# VHN-B.net
KiCad netlist of a schematic drawn in EAGLE
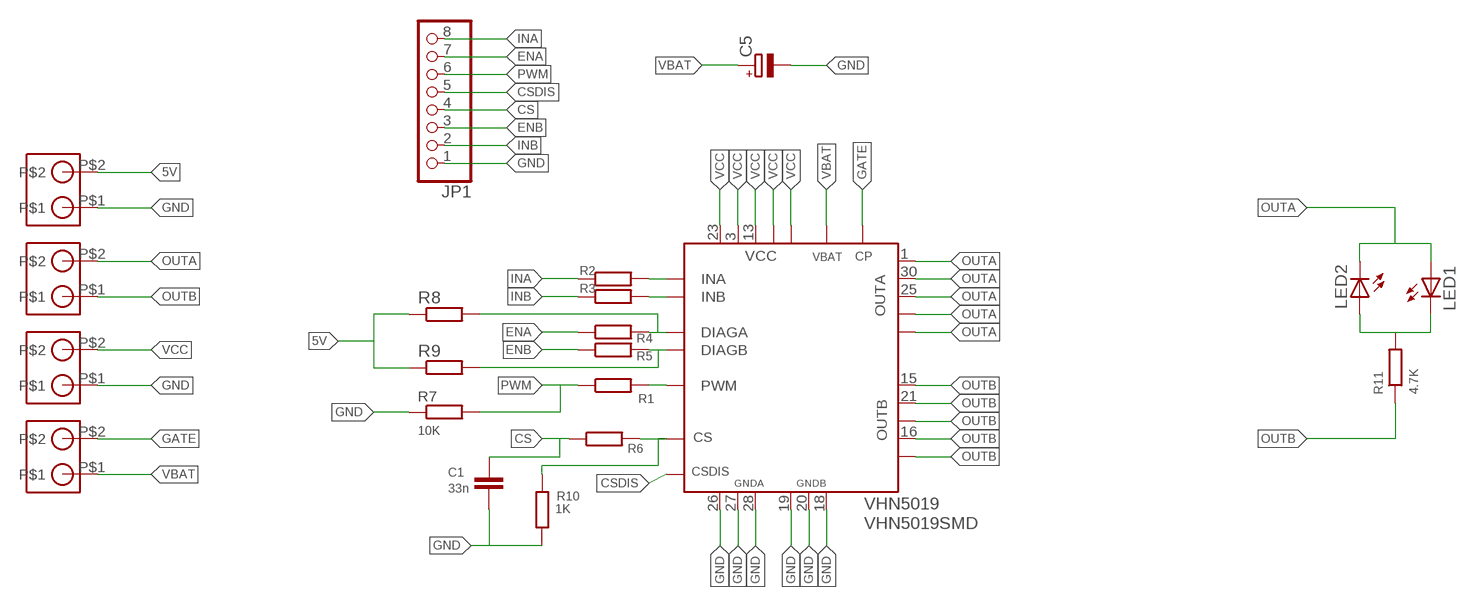
[diagram p0: schematic, sheet 1]

(export (version "E")
  (design (tool "Eeschema 10.0.6"))
  (components
    (comp (ref "C1")
      (value "33n")
      (footprint "eagle-import:C0402")
      (libsource (lib "eagle-import") (part "C-EUC0402"))
    )
    (comp (ref "C5")
      (value "CPOL-EUE2,5-6E")
      (footprint "eagle-import:E2,5-6E")
      (libsource (lib "eagle-import") (part "CPOL-EUE2,5-6E"))
    )
    (comp (ref "JP1")
      (value "PINHD-1X8")
      (footprint "eagle-import:1X08")
      (libsource (lib "eagle-import") (part "PINHD-1X8"))
    )
    (comp (ref "LED1")
      (value "LEDCHIPLED_0603")
      (footprint "eagle-import:CHIPLED_0603")
      (libsource (lib "eagle-import") (part "LEDCHIPLED_0603"))
    )
    (comp (ref "LED2")
      (value "LEDCHIPLED_0603")
      (footprint "eagle-import:CHIPLED_0603")
      (libsource (lib "eagle-import") (part "LEDCHIPLED_0603"))
    )
    (comp (ref "R1")
      (value "R-EU_R0402")
      (footprint "eagle-import:R0402")
      (libsource (lib "eagle-import") (part "R-EU_R0402"))
    )
    (comp (ref "R2")
      (value "R-EU_R0402")
      (footprint "eagle-import:R0402")
      (libsource (lib "eagle-import") (part "R-EU_R0402"))
    )
    (comp (ref "R3")
      (value "R-EU_R0402")
      (footprint "eagle-import:R0402")
      (libsource (lib "eagle-import") (part "R-EU_R0402"))
    )
    (comp (ref "R4")
      (value "R-EU_R0402")
      (footprint "eagle-import:R0402")
      (libsource (lib "eagle-import") (part "R-EU_R0402"))
    )
    (comp (ref "R5")
      (value "R-EU_R0402")
      (footprint "eagle-import:R0402")
      (libsource (lib "eagle-import") (part "R-EU_R0402"))
    )
    (comp (ref "R6")
      (value "R-EU_R0402")
      (footprint "eagle-import:R0402")
      (libsource (lib "eagle-import") (part "R-EU_R0402"))
    )
    (comp (ref "R7")
      (value "10K")
      (footprint "eagle-import:R0402")
      (libsource (lib "eagle-import") (part "R-EU_R0402"))
    )
    (comp (ref "R8")
      (value "R-EU_R0402")
      (footprint "eagle-import:R0402")
      (libsource (lib "eagle-import") (part "R-EU_R0402"))
    )
    (comp (ref "R9")
      (value "R-EU_R0402")
      (footprint "eagle-import:R0402")
      (libsource (lib "eagle-import") (part "R-EU_R0402"))
    )
    (comp (ref "R10")
      (value "1K")
      (footprint "eagle-import:R0402")
      (libsource (lib "eagle-import") (part "R-EU_R0402"))
    )
    (comp (ref "R11")
      (value "4.7K")
      (footprint "eagle-import:R0402")
      (libsource (lib "eagle-import") (part "R-EU_R0402"))
    )
    (comp (ref "U$1")
      (value "PBCON")
      (footprint "eagle-import:02P")
      (libsource (lib "eagle-import") (part "PBCON"))
    )
    (comp (ref "U$2")
      (value "PBCON")
      (footprint "eagle-import:02P")
      (libsource (lib "eagle-import") (part "PBCON"))
    )
    (comp (ref "U$3")
      (value "PBCON")
      (footprint "eagle-import:02P")
      (libsource (lib "eagle-import") (part "PBCON"))
    )
    (comp (ref "U$4")
      (value "PBCON")
      (footprint "eagle-import:02P")
      (libsource (lib "eagle-import") (part "PBCON"))
    )
    (comp (ref "VHN5019")
      (value "VHN5019SMD")
      (footprint "eagle-import:SO-30")
      (libsource (lib "eagle-import") (part "VHN5019SMD"))
    )
  )
  (nets
    (net (code "1") (name "5V") (class "Default")
      (node (ref "R8") (pin "1") (pinfunction "1_1") (pintype "passive"))
      (node (ref "R9") (pin "1") (pinfunction "1_1") (pintype "passive"))
      (node (ref "U$4") (pin "P$2") (pinfunction "P$2_P$2") (pintype "bidirectional"))
    )
    (net (code "2") (name "CS") (class "Default")
      (node (ref "C1") (pin "1") (pinfunction "1_1") (pintype "passive"))
      (node (ref "JP1") (pin "4") (pinfunction "4_4") (pintype "passive"))
      (node (ref "R6") (pin "1") (pinfunction "1_1") (pintype "passive"))
    )
    (net (code "3") (name "CSDIS") (class "Default")
      (node (ref "JP1") (pin "5") (pinfunction "5_5") (pintype "passive"))
      (node (ref "VHN5019") (pin "6") (pinfunction "CSDIS_6") (pintype "bidirectional"))
    )
    (net (code "4") (name "ENA") (class "Default")
      (node (ref "JP1") (pin "7") (pinfunction "7_7") (pintype "passive"))
      (node (ref "R4") (pin "1") (pinfunction "1_1") (pintype "passive"))
    )
    (net (code "5") (name "ENB") (class "Default")
      (node (ref "JP1") (pin "3") (pinfunction "3_3") (pintype "passive"))
      (node (ref "R5") (pin "1") (pinfunction "1_1") (pintype "passive"))
    )
    (net (code "6") (name "GATE") (class "Default")
      (node (ref "U$3") (pin "P$2") (pinfunction "P$2_P$2") (pintype "bidirectional"))
      (node (ref "VHN5019") (pin "11") (pinfunction "CP_11") (pintype "bidirectional"))
    )
    (net (code "7") (name "GND") (class "Default")
      (node (ref "C1") (pin "2") (pinfunction "2_2") (pintype "passive"))
      (node (ref "C5") (pin "-") (pinfunction "-_-") (pintype "passive"))
      (node (ref "JP1") (pin "1") (pinfunction "1_1") (pintype "passive"))
      (node (ref "R10") (pin "1") (pinfunction "1_1") (pintype "passive"))
      (node (ref "R7") (pin "1") (pinfunction "1_1") (pintype "passive"))
      (node (ref "U$1") (pin "P$1") (pinfunction "P$1_P$1") (pintype "bidirectional"))
      (node (ref "U$4") (pin "P$1") (pinfunction "P$1_P$1") (pintype "bidirectional"))
      (node (ref "VHN5019") (pin "18") (pinfunction "GNDB_18") (pintype "power_in"))
      (node (ref "VHN5019") (pin "19") (pinfunction "GNDB_19") (pintype "power_in"))
      (node (ref "VHN5019") (pin "20") (pinfunction "GNDB_20") (pintype "power_in"))
      (node (ref "VHN5019") (pin "26") (pinfunction "GNDA_26") (pintype "power_in"))
      (node (ref "VHN5019") (pin "27") (pinfunction "GNDA_27") (pintype "power_in"))
      (node (ref "VHN5019") (pin "28") (pinfunction "GNDA_28") (pintype "power_in"))
    )
    (net (code "8") (name "INA") (class "Default")
      (node (ref "JP1") (pin "8") (pinfunction "8_8") (pintype "passive"))
      (node (ref "R2") (pin "1") (pinfunction "1_1") (pintype "passive"))
    )
    (net (code "9") (name "INB") (class "Default")
      (node (ref "JP1") (pin "2") (pinfunction "2_2") (pintype "passive"))
      (node (ref "R3") (pin "1") (pinfunction "1_1") (pintype "passive"))
    )
    (net (code "10") (name "Net-(LED1-PadC)") (class "Default")
      (node (ref "LED1") (pin "C") (pinfunction "C_C") (pintype "passive"))
      (node (ref "LED2") (pin "A") (pinfunction "A_A") (pintype "passive"))
      (node (ref "R11") (pin "2") (pinfunction "2_2") (pintype "passive"))
    )
    (net (code "11") (name "Net-(VHN5019-CS)") (class "Default")
      (node (ref "R10") (pin "2") (pinfunction "2_2") (pintype "passive"))
      (node (ref "R6") (pin "2") (pinfunction "2_2") (pintype "passive"))
      (node (ref "VHN5019") (pin "8") (pinfunction "CS_8") (pintype "bidirectional"))
    )
    (net (code "12") (name "Net-(VHN5019-DIAGA)") (class "Default")
      (node (ref "R4") (pin "2") (pinfunction "2_2") (pintype "passive"))
      (node (ref "R8") (pin "2") (pinfunction "2_2") (pintype "passive"))
      (node (ref "VHN5019") (pin "5") (pinfunction "DIAGA_5") (pintype "open_collector"))
    )
    (net (code "13") (name "Net-(VHN5019-DIAGB)") (class "Default")
      (node (ref "R5") (pin "2") (pinfunction "2_2") (pintype "passive"))
      (node (ref "R9") (pin "2") (pinfunction "2_2") (pintype "passive"))
      (node (ref "VHN5019") (pin "9") (pinfunction "DIAGB_9") (pintype "open_collector"))
    )
    (net (code "14") (name "Net-(VHN5019-INA)") (class "Default")
      (node (ref "R2") (pin "2") (pinfunction "2_2") (pintype "passive"))
      (node (ref "VHN5019") (pin "4") (pinfunction "INA_4") (pintype "input"))
    )
    (net (code "15") (name "Net-(VHN5019-INB)") (class "Default")
      (node (ref "R3") (pin "2") (pinfunction "2_2") (pintype "passive"))
      (node (ref "VHN5019") (pin "10") (pinfunction "INB_10") (pintype "input"))
    )
    (net (code "16") (name "Net-(VHN5019-PWM)") (class "Default")
      (node (ref "R1") (pin "2") (pinfunction "2_2") (pintype "passive"))
      (node (ref "VHN5019") (pin "7") (pinfunction "PWM_7") (pintype "input"))
    )
    (net (code "17") (name "OUTA") (class "Default")
      (node (ref "LED1") (pin "A") (pinfunction "A_A") (pintype "passive"))
      (node (ref "LED2") (pin "C") (pinfunction "C_C") (pintype "passive"))
      (node (ref "U$2") (pin "P$2") (pinfunction "P$2_P$2") (pintype "bidirectional"))
      (node (ref "VHN5019") (pin "1") (pinfunction "OUTA_1") (pintype "output"))
      (node (ref "VHN5019") (pin "25") (pinfunction "OUTA_25") (pintype "passive"))
      (node (ref "VHN5019") (pin "30") (pinfunction "OUTA_30") (pintype "passive"))
      (node (ref "VHN5019") (pin "OUTA") (pinfunction "OUTA_OUTA") (pintype "passive"))
      (node (ref "VHN5019") (pin "OUTA@1") (pinfunction "OUTA_OUTA@1") (pintype "passive"))
    )
    (net (code "18") (name "OUTB") (class "Default")
      (node (ref "R11") (pin "1") (pinfunction "1_1") (pintype "passive"))
      (node (ref "U$2") (pin "P$1") (pinfunction "P$1_P$1") (pintype "bidirectional"))
      (node (ref "VHN5019") (pin "15") (pinfunction "OUTB_15") (pintype "passive"))
      (node (ref "VHN5019") (pin "16") (pinfunction "OUTB_16") (pintype "output"))
      (node (ref "VHN5019") (pin "21") (pinfunction "OUTB_21") (pintype "passive"))
      (node (ref "VHN5019") (pin "OUTB") (pinfunction "OUTB_OUTB") (pintype "passive"))
      (node (ref "VHN5019") (pin "OUTB@1") (pinfunction "OUTB_OUTB@1") (pintype "passive"))
    )
    (net (code "19") (name "PWM") (class "Default")
      (node (ref "JP1") (pin "6") (pinfunction "6_6") (pintype "passive"))
      (node (ref "R1") (pin "1") (pinfunction "1_1") (pintype "passive"))
      (node (ref "R7") (pin "2") (pinfunction "2_2") (pintype "passive"))
    )
    (net (code "20") (name "VBAT") (class "Default")
      (node (ref "C5") (pin "+") (pinfunction "+_+") (pintype "passive"))
      (node (ref "U$3") (pin "P$1") (pinfunction "P$1_P$1") (pintype "bidirectional"))
      (node (ref "VHN5019") (pin "12") (pinfunction "VBAT_12") (pintype "bidirectional"))
    )
    (net (code "21") (name "VCC") (class "Default")
      (node (ref "U$1") (pin "P$2") (pinfunction "P$2_P$2") (pintype "bidirectional"))
      (node (ref "VHN5019") (pin "13") (pinfunction "VCC_13") (pintype "power_in"))
      (node (ref "VHN5019") (pin "23") (pinfunction "VCC_23") (pintype "power_in"))
      (node (ref "VHN5019") (pin "3") (pinfunction "VCC_3") (pintype "power_in"))
      (node (ref "VHN5019") (pin "VCC") (pinfunction "VCC_VCC") (pintype "power_in"))
      (node (ref "VHN5019") (pin "VCC@1") (pinfunction "VCC_VCC@1") (pintype "power_in"))
    )
  )
)
